# IoTSensorBoard.net
KiCad netlist of a schematic drawn in EAGLE
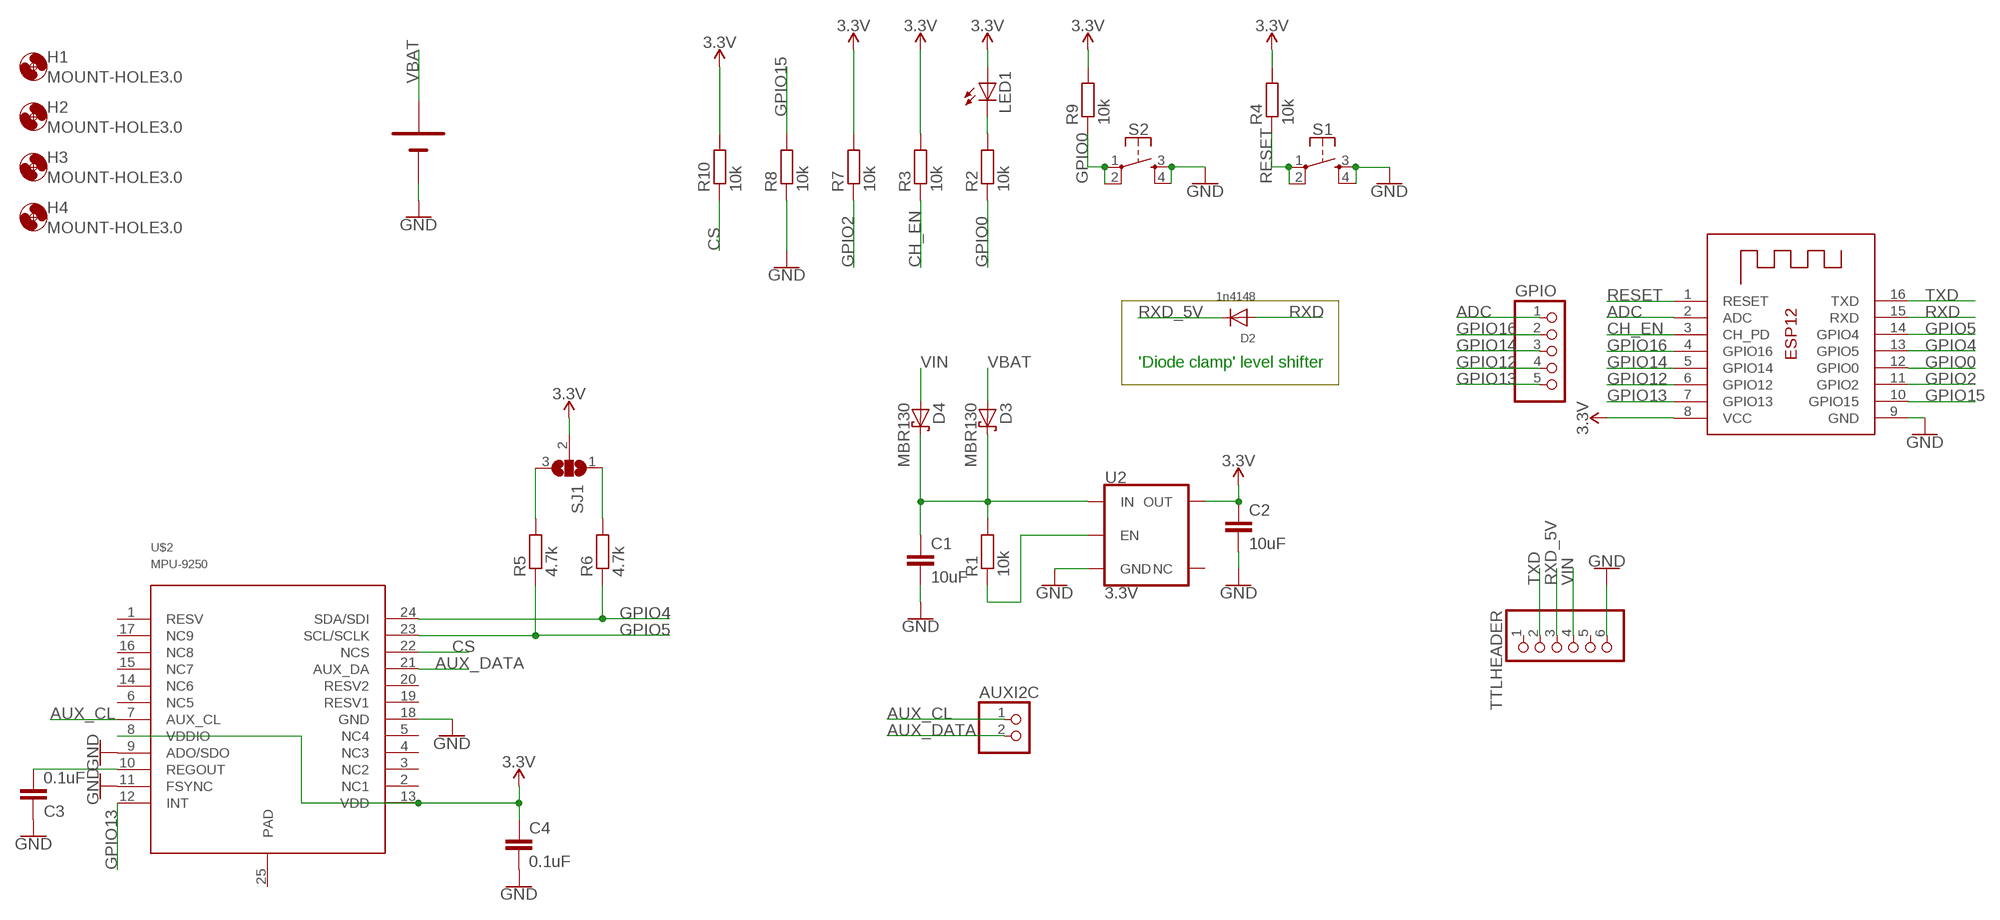
[diagram p0: schematic, sheet 1]

(export (version "E")
  (design (tool "Eeschema 10.0.6"))
  (components
    (comp (ref "AUXI2C")
      (value "PINHD-1X2")
      (footprint "eagle-import:1X02")
      (libsource (lib "eagle-import") (part "PINHD-1X2"))
    )
    (comp (ref "C1")
      (value "10uF")
      (footprint "eagle-import:C0805")
      (libsource (lib "eagle-import") (part "C-EUC0805"))
    )
    (comp (ref "C2")
      (value "10uF")
      (footprint "eagle-import:C0805")
      (libsource (lib "eagle-import") (part "C-EUC0805"))
    )
    (comp (ref "C3")
      (value "0.1uF")
      (footprint "eagle-import:C0805")
      (libsource (lib "eagle-import") (part "C-EUC0805"))
    )
    (comp (ref "C4")
      (value "0.1uF")
      (footprint "eagle-import:C0805")
      (libsource (lib "eagle-import") (part "C-EUC0805"))
    )
    (comp (ref "D2")
      (value "1n4148")
      (footprint "eagle-import:SMADIODE")
      (libsource (lib "eagle-import") (part "DIODESMA"))
    )
    (comp (ref "D3")
      (value "MBR130")
      (footprint "eagle-import:SMB")
      (libsource (lib "eagle-import") (part "MBRS130LT3"))
    )
    (comp (ref "D4")
      (value "MBR130")
      (footprint "eagle-import:SMB")
      (libsource (lib "eagle-import") (part "MBRS130LT3"))
    )
    (comp (ref "GPIO")
      (value "PINHD-1X5")
      (footprint "eagle-import:1X05")
      (libsource (lib "eagle-import") (part "PINHD-1X5"))
    )
    (comp (ref "H1")
      (value "MOUNT-HOLE3.0")
      (footprint "eagle-import:3,0")
      (libsource (lib "eagle-import") (part "MOUNT-HOLE3.0"))
    )
    (comp (ref "H2")
      (value "MOUNT-HOLE3.0")
      (footprint "eagle-import:3,0")
      (libsource (lib "eagle-import") (part "MOUNT-HOLE3.0"))
    )
    (comp (ref "H3")
      (value "MOUNT-HOLE3.0")
      (footprint "eagle-import:3,0")
      (libsource (lib "eagle-import") (part "MOUNT-HOLE3.0"))
    )
    (comp (ref "H4")
      (value "MOUNT-HOLE3.0")
      (footprint "eagle-import:3,0")
      (libsource (lib "eagle-import") (part "MOUNT-HOLE3.0"))
    )
    (comp (ref "LED1")
      (value "LEDCHIP-LED0805")
      (footprint "eagle-import:CHIP-LED0805")
      (libsource (lib "eagle-import") (part "LEDCHIP-LED0805"))
    )
    (comp (ref "R1")
      (value "10k")
      (footprint "eagle-import:R0805")
      (libsource (lib "eagle-import") (part "R-EU_R0805"))
    )
    (comp (ref "R2")
      (value "10k")
      (footprint "eagle-import:R0805")
      (libsource (lib "eagle-import") (part "R-EU_R0805"))
    )
    (comp (ref "R3")
      (value "10k")
      (footprint "eagle-import:R0805")
      (libsource (lib "eagle-import") (part "R-EU_R0805"))
    )
    (comp (ref "R4")
      (value "10k")
      (footprint "eagle-import:R0805")
      (libsource (lib "eagle-import") (part "R-EU_R0805"))
    )
    (comp (ref "R5")
      (value "4.7k")
      (footprint "eagle-import:R0805")
      (libsource (lib "eagle-import") (part "R-EU_R0805"))
    )
    (comp (ref "R6")
      (value "4.7k")
      (footprint "eagle-import:R0805")
      (libsource (lib "eagle-import") (part "R-EU_R0805"))
    )
    (comp (ref "R7")
      (value "10k")
      (footprint "eagle-import:R0805")
      (libsource (lib "eagle-import") (part "R-EU_R0805"))
    )
    (comp (ref "R8")
      (value "10k")
      (footprint "eagle-import:R0805")
      (libsource (lib "eagle-import") (part "R-EU_R0805"))
    )
    (comp (ref "R9")
      (value "10k")
      (footprint "eagle-import:R0805")
      (libsource (lib "eagle-import") (part "R-EU_R0805"))
    )
    (comp (ref "R10")
      (value "10k")
      (footprint "eagle-import:R0805")
      (libsource (lib "eagle-import") (part "R-EU_R0805"))
    )
    (comp (ref "S1")
      (value "MOMENTARY-SWITCH-SPST-2-SMD-5.2MM")
      (footprint "eagle-import:TACTILE_SWITCH_SMD_5.2MM")
      (libsource (lib "eagle-import") (part "MOMENTARY-SWITCH-SPST-2-SMD-5.2MM"))
    )
    (comp (ref "S2")
      (value "MOMENTARY-SWITCH-SPST-2-SMD-5.2MM")
      (footprint "eagle-import:TACTILE_SWITCH_SMD_5.2MM")
      (libsource (lib "eagle-import") (part "MOMENTARY-SWITCH-SPST-2-SMD-5.2MM"))
    )
    (comp (ref "SJ1")
      (value "SJ2W")
      (footprint "eagle-import:SJ_2")
      (libsource (lib "eagle-import") (part "SJ2W"))
    )
    (comp (ref "TTLHEADER")
      (value "PINHD-1X6")
      (footprint "eagle-import:1X06")
      (libsource (lib "eagle-import") (part "PINHD-1X6"))
    )
    (comp (ref "U$1")
      (value "SMTU_2450N")
      (footprint "eagle-import:SMTU_2450N")
      (libsource (lib "eagle-import") (part "SMTU_2450N"))
    )
    (comp (ref "U$2")
      (value "MPU-9250")
      (footprint "eagle-import:LEAD-QFN24")
      (libsource (lib "eagle-import") (part "MPU-9250"))
    )
    (comp (ref "U2")
      (value "3.3V")
      (footprint "eagle-import:SOT23-5")
      (libsource (lib "eagle-import") (part "V_REG_AP2112K-3.3V"))
    )
    (comp (ref "X1")
      (value "ESP-12")
      (footprint "eagle-import:ESP-12")
      (libsource (lib "eagle-import") (part "ESP-12"))
    )
  )
  (nets
    (net (code "1") (name "/ADC") (class "Default")
      (node (ref "GPIO") (pin "1") (pinfunction "1_1") (pintype "passive"))
      (node (ref "X1") (pin "2") (pinfunction "ADC_2") (pintype "passive"))
    )
    (net (code "2") (name "/AUX_CL") (class "Default")
      (node (ref "AUXI2C") (pin "1") (pinfunction "1_1") (pintype "passive"))
      (node (ref "U$2") (pin "7") (pinfunction "AUX_CL_7") (pintype "bidirectional"))
    )
    (net (code "3") (name "/AUX_DATA") (class "Default")
      (node (ref "AUXI2C") (pin "2") (pinfunction "2_2") (pintype "passive"))
      (node (ref "U$2") (pin "21") (pinfunction "AUX_DA_21") (pintype "bidirectional"))
    )
    (net (code "4") (name "/CH_EN") (class "Default")
      (node (ref "R3") (pin "1") (pinfunction "1_1") (pintype "passive"))
      (node (ref "X1") (pin "3") (pinfunction "CH_PD_3") (pintype "input"))
    )
    (net (code "5") (name "/CS") (class "Default")
      (node (ref "R10") (pin "1") (pinfunction "1_1") (pintype "passive"))
      (node (ref "U$2") (pin "22") (pinfunction "NCS_22") (pintype "bidirectional"))
    )
    (net (code "6") (name "/GPIO0") (class "Default")
      (node (ref "R2") (pin "1") (pinfunction "1_1") (pintype "passive"))
      (node (ref "R9") (pin "1") (pinfunction "1_1") (pintype "passive"))
      (node (ref "S2") (pin "1") (pinfunction "1_1") (pintype "passive"))
      (node (ref "S2") (pin "2") (pinfunction "2_2") (pintype "passive"))
      (node (ref "X1") (pin "12") (pinfunction "GPIO0_12") (pintype "bidirectional"))
    )
    (net (code "7") (name "/GPIO2") (class "Default")
      (node (ref "R7") (pin "1") (pinfunction "1_1") (pintype "passive"))
      (node (ref "X1") (pin "11") (pinfunction "GPIO2_11") (pintype "bidirectional"))
    )
    (net (code "8") (name "/GPIO4") (class "Default")
      (node (ref "R6") (pin "1") (pinfunction "1_1") (pintype "passive"))
      (node (ref "U$2") (pin "24") (pinfunction "SDA/SDI_24") (pintype "bidirectional"))
      (node (ref "X1") (pin "13") (pinfunction "GPIO5_13") (pintype "bidirectional"))
    )
    (net (code "9") (name "/GPIO5") (class "Default")
      (node (ref "R5") (pin "1") (pinfunction "1_1") (pintype "passive"))
      (node (ref "U$2") (pin "23") (pinfunction "SCL/SCLK_23") (pintype "bidirectional"))
      (node (ref "X1") (pin "14") (pinfunction "GPIO4_14") (pintype "bidirectional"))
    )
    (net (code "10") (name "/GPIO12") (class "Default")
      (node (ref "GPIO") (pin "4") (pinfunction "4_4") (pintype "passive"))
      (node (ref "X1") (pin "6") (pinfunction "GPIO12_6") (pintype "bidirectional"))
    )
    (net (code "11") (name "/GPIO13") (class "Default")
      (node (ref "GPIO") (pin "5") (pinfunction "5_5") (pintype "passive"))
      (node (ref "U$2") (pin "12") (pinfunction "INT_12") (pintype "bidirectional"))
      (node (ref "X1") (pin "7") (pinfunction "GPIO13_7") (pintype "bidirectional"))
    )
    (net (code "12") (name "/GPIO14") (class "Default")
      (node (ref "GPIO") (pin "3") (pinfunction "3_3") (pintype "passive"))
      (node (ref "X1") (pin "5") (pinfunction "GPIO14_5") (pintype "bidirectional"))
    )
    (net (code "13") (name "/GPIO15") (class "Default")
      (node (ref "R8") (pin "2") (pinfunction "2_2") (pintype "passive"))
      (node (ref "X1") (pin "10") (pinfunction "GPIO15_10") (pintype "bidirectional"))
    )
    (net (code "14") (name "/GPIO16") (class "Default")
      (node (ref "GPIO") (pin "2") (pinfunction "2_2") (pintype "passive"))
      (node (ref "X1") (pin "4") (pinfunction "GPIO16_4") (pintype "bidirectional"))
    )
    (net (code "15") (name "/RESET") (class "Default")
      (node (ref "R4") (pin "1") (pinfunction "1_1") (pintype "passive"))
      (node (ref "S1") (pin "1") (pinfunction "1_1") (pintype "passive"))
      (node (ref "S1") (pin "2") (pinfunction "2_2") (pintype "passive"))
      (node (ref "X1") (pin "1") (pinfunction "RESET_1") (pintype "input"))
    )
    (net (code "16") (name "/RXD") (class "Default")
      (node (ref "D2") (pin "A") (pinfunction "A_A") (pintype "passive"))
      (node (ref "X1") (pin "15") (pinfunction "RXD_15") (pintype "input"))
    )
    (net (code "17") (name "/RXD_5V") (class "Default")
      (node (ref "D2") (pin "C") (pinfunction "C_C") (pintype "passive"))
      (node (ref "TTLHEADER") (pin "3") (pinfunction "3_3") (pintype "passive"))
    )
    (net (code "18") (name "/TXD") (class "Default")
      (node (ref "TTLHEADER") (pin "2") (pinfunction "2_2") (pintype "passive"))
      (node (ref "X1") (pin "16") (pinfunction "TXD_16") (pintype "output"))
    )
    (net (code "19") (name "/VBAT") (class "Default")
      (node (ref "D3") (pin "A") (pinfunction "A_A") (pintype "passive"))
      (node (ref "U$1") (pin "P$2") (pinfunction "P$2P_P$2") (pintype "bidirectional"))
    )
    (net (code "20") (name "/VIN") (class "Default")
      (node (ref "D4") (pin "A") (pinfunction "A_A") (pintype "passive"))
      (node (ref "TTLHEADER") (pin "4") (pinfunction "4_4") (pintype "passive"))
    )
    (net (code "21") (name "3.3V") (class "Default")
      (node (ref "C2") (pin "1") (pinfunction "1_1") (pintype "passive"))
      (node (ref "C4") (pin "1") (pinfunction "1_1") (pintype "passive"))
      (node (ref "LED1") (pin "A") (pinfunction "A_A") (pintype "passive"))
      (node (ref "R10") (pin "2") (pinfunction "2_2") (pintype "passive"))
      (node (ref "R3") (pin "2") (pinfunction "2_2") (pintype "passive"))
      (node (ref "R4") (pin "2") (pinfunction "2_2") (pintype "passive"))
      (node (ref "R7") (pin "2") (pinfunction "2_2") (pintype "passive"))
      (node (ref "R9") (pin "2") (pinfunction "2_2") (pintype "passive"))
      (node (ref "SJ1") (pin "2") (pinfunction "2_2") (pintype "passive"))
      (node (ref "U$2") (pin "13") (pinfunction "VDD_13") (pintype "bidirectional"))
      (node (ref "U$2") (pin "8") (pinfunction "VDDIO_8") (pintype "bidirectional"))
      (node (ref "U2") (pin "5") (pinfunction "OUT_5") (pintype "passive"))
      (node (ref "X1") (pin "8") (pinfunction "VCC_8") (pintype "power_in"))
    )
    (net (code "22") (name "GND") (class "Default")
      (node (ref "C1") (pin "2") (pinfunction "2_2") (pintype "passive"))
      (node (ref "C2") (pin "2") (pinfunction "2_2") (pintype "passive"))
      (node (ref "C3") (pin "1") (pinfunction "1_1") (pintype "passive"))
      (node (ref "C4") (pin "2") (pinfunction "2_2") (pintype "passive"))
      (node (ref "R8") (pin "1") (pinfunction "1_1") (pintype "passive"))
      (node (ref "S1") (pin "3") (pinfunction "3_3") (pintype "passive"))
      (node (ref "S1") (pin "4") (pinfunction "4_4") (pintype "passive"))
      (node (ref "S2") (pin "3") (pinfunction "3_3") (pintype "passive"))
      (node (ref "S2") (pin "4") (pinfunction "4_4") (pintype "passive"))
      (node (ref "TTLHEADER") (pin "6") (pinfunction "6_6") (pintype "passive"))
      (node (ref "U$1") (pin "P$1") (pinfunction "P$1N_P$1") (pintype "bidirectional"))
      (node (ref "U$2") (pin "11") (pinfunction "FSYNC_11") (pintype "bidirectional"))
      (node (ref "U$2") (pin "18") (pinfunction "GND_18") (pintype "bidirectional"))
      (node (ref "U$2") (pin "9") (pinfunction "ADO/SDO_9") (pintype "bidirectional"))
      (node (ref "U2") (pin "2") (pinfunction "GND_2") (pintype "input"))
      (node (ref "X1") (pin "9") (pinfunction "GND_9") (pintype "power_in"))
    )
    (net (code "23") (name "Net-(LED1-PadC)") (class "Default")
      (node (ref "LED1") (pin "C") (pinfunction "C_C") (pintype "passive"))
      (node (ref "R2") (pin "2") (pinfunction "2_2") (pintype "passive"))
    )
    (net (code "24") (name "Net-(R5-Pad2)") (class "Default")
      (node (ref "R5") (pin "2") (pinfunction "2_2") (pintype "passive"))
      (node (ref "SJ1") (pin "3") (pinfunction "3_3") (pintype "passive"))
    )
    (net (code "25") (name "Net-(R6-Pad2)") (class "Default")
      (node (ref "R6") (pin "2") (pinfunction "2_2") (pintype "passive"))
      (node (ref "SJ1") (pin "1") (pinfunction "1_1") (pintype "passive"))
    )
    (net (code "26") (name "Net-(U$2-REGOUT)") (class "Default")
      (node (ref "C3") (pin "2") (pinfunction "2_2") (pintype "passive"))
      (node (ref "U$2") (pin "10") (pinfunction "REGOUT_10") (pintype "bidirectional"))
    )
    (net (code "27") (name "Net-(U2-EN)") (class "Default")
      (node (ref "R1") (pin "1") (pinfunction "1_1") (pintype "passive"))
      (node (ref "U2") (pin "3") (pinfunction "EN_3") (pintype "input"))
    )
    (net (code "28") (name "Net-(U2-IN)") (class "Default")
      (node (ref "C1") (pin "1") (pinfunction "1_1") (pintype "passive"))
      (node (ref "D3") (pin "C") (pinfunction "C_C") (pintype "passive"))
      (node (ref "D4") (pin "C") (pinfunction "C_C") (pintype "passive"))
      (node (ref "R1") (pin "2") (pinfunction "2_2") (pintype "passive"))
      (node (ref "U2") (pin "1") (pinfunction "IN_1") (pintype "input"))
    )
    (net (code "29") (name "unconnected-(TTLHEADER-Pad1)") (class "Default")
      (node (ref "TTLHEADER") (pin "1") (pinfunction "1_1") (pintype "passive"))
    )
    (net (code "30") (name "unconnected-(TTLHEADER-Pad5)") (class "Default")
      (node (ref "TTLHEADER") (pin "5") (pinfunction "5_5") (pintype "passive"))
    )
    (net (code "31") (name "unconnected-(U$2-NC1-Pad2)") (class "Default")
      (node (ref "U$2") (pin "2") (pinfunction "NC1_2") (pintype "bidirectional"))
    )
    (net (code "32") (name "unconnected-(U$2-NC2-Pad3)") (class "Default")
      (node (ref "U$2") (pin "3") (pinfunction "NC2_3") (pintype "bidirectional"))
    )
    (net (code "33") (name "unconnected-(U$2-NC3-Pad4)") (class "Default")
      (node (ref "U$2") (pin "4") (pinfunction "NC3_4") (pintype "bidirectional"))
    )
    (net (code "34") (name "unconnected-(U$2-NC4-Pad5)") (class "Default")
      (node (ref "U$2") (pin "5") (pinfunction "NC4_5") (pintype "bidirectional"))
    )
    (net (code "35") (name "unconnected-(U$2-NC5-Pad6)") (class "Default")
      (node (ref "U$2") (pin "6") (pinfunction "NC5_6") (pintype "bidirectional"))
    )
    (net (code "36") (name "unconnected-(U$2-NC6-Pad14)") (class "Default")
      (node (ref "U$2") (pin "14") (pinfunction "NC6_14") (pintype "bidirectional"))
    )
    (net (code "37") (name "unconnected-(U$2-NC7-Pad15)") (class "Default")
      (node (ref "U$2") (pin "15") (pinfunction "NC7_15") (pintype "bidirectional"))
    )
    (net (code "38") (name "unconnected-(U$2-NC8-Pad16)") (class "Default")
      (node (ref "U$2") (pin "16") (pinfunction "NC8_16") (pintype "bidirectional"))
    )
    (net (code "39") (name "unconnected-(U$2-NC9-Pad17)") (class "Default")
      (node (ref "U$2") (pin "17") (pinfunction "NC9_17") (pintype "bidirectional"))
    )
    (net (code "40") (name "unconnected-(U$2-PAD-Pad25)") (class "Default")
      (node (ref "U$2") (pin "25") (pinfunction "PAD_25") (pintype "bidirectional"))
    )
    (net (code "41") (name "unconnected-(U$2-RESV-Pad1)") (class "Default")
      (node (ref "U$2") (pin "1") (pinfunction "RESV_1") (pintype "bidirectional"))
    )
    (net (code "42") (name "unconnected-(U$2-RESV1-Pad19)") (class "Default")
      (node (ref "U$2") (pin "19") (pinfunction "RESV1_19") (pintype "bidirectional"))
    )
    (net (code "43") (name "unconnected-(U$2-RESV2-Pad20)") (class "Default")
      (node (ref "U$2") (pin "20") (pinfunction "RESV2_20") (pintype "bidirectional"))
    )
    (net (code "44") (name "unconnected-(U2-NC-Pad4)") (class "Default")
      (node (ref "U2") (pin "4") (pinfunction "NC_4") (pintype "no_connect"))
    )
  )
)
